# MRCS-12v-power-block.net
KiCad netlist of a schematic drawn in EAGLE
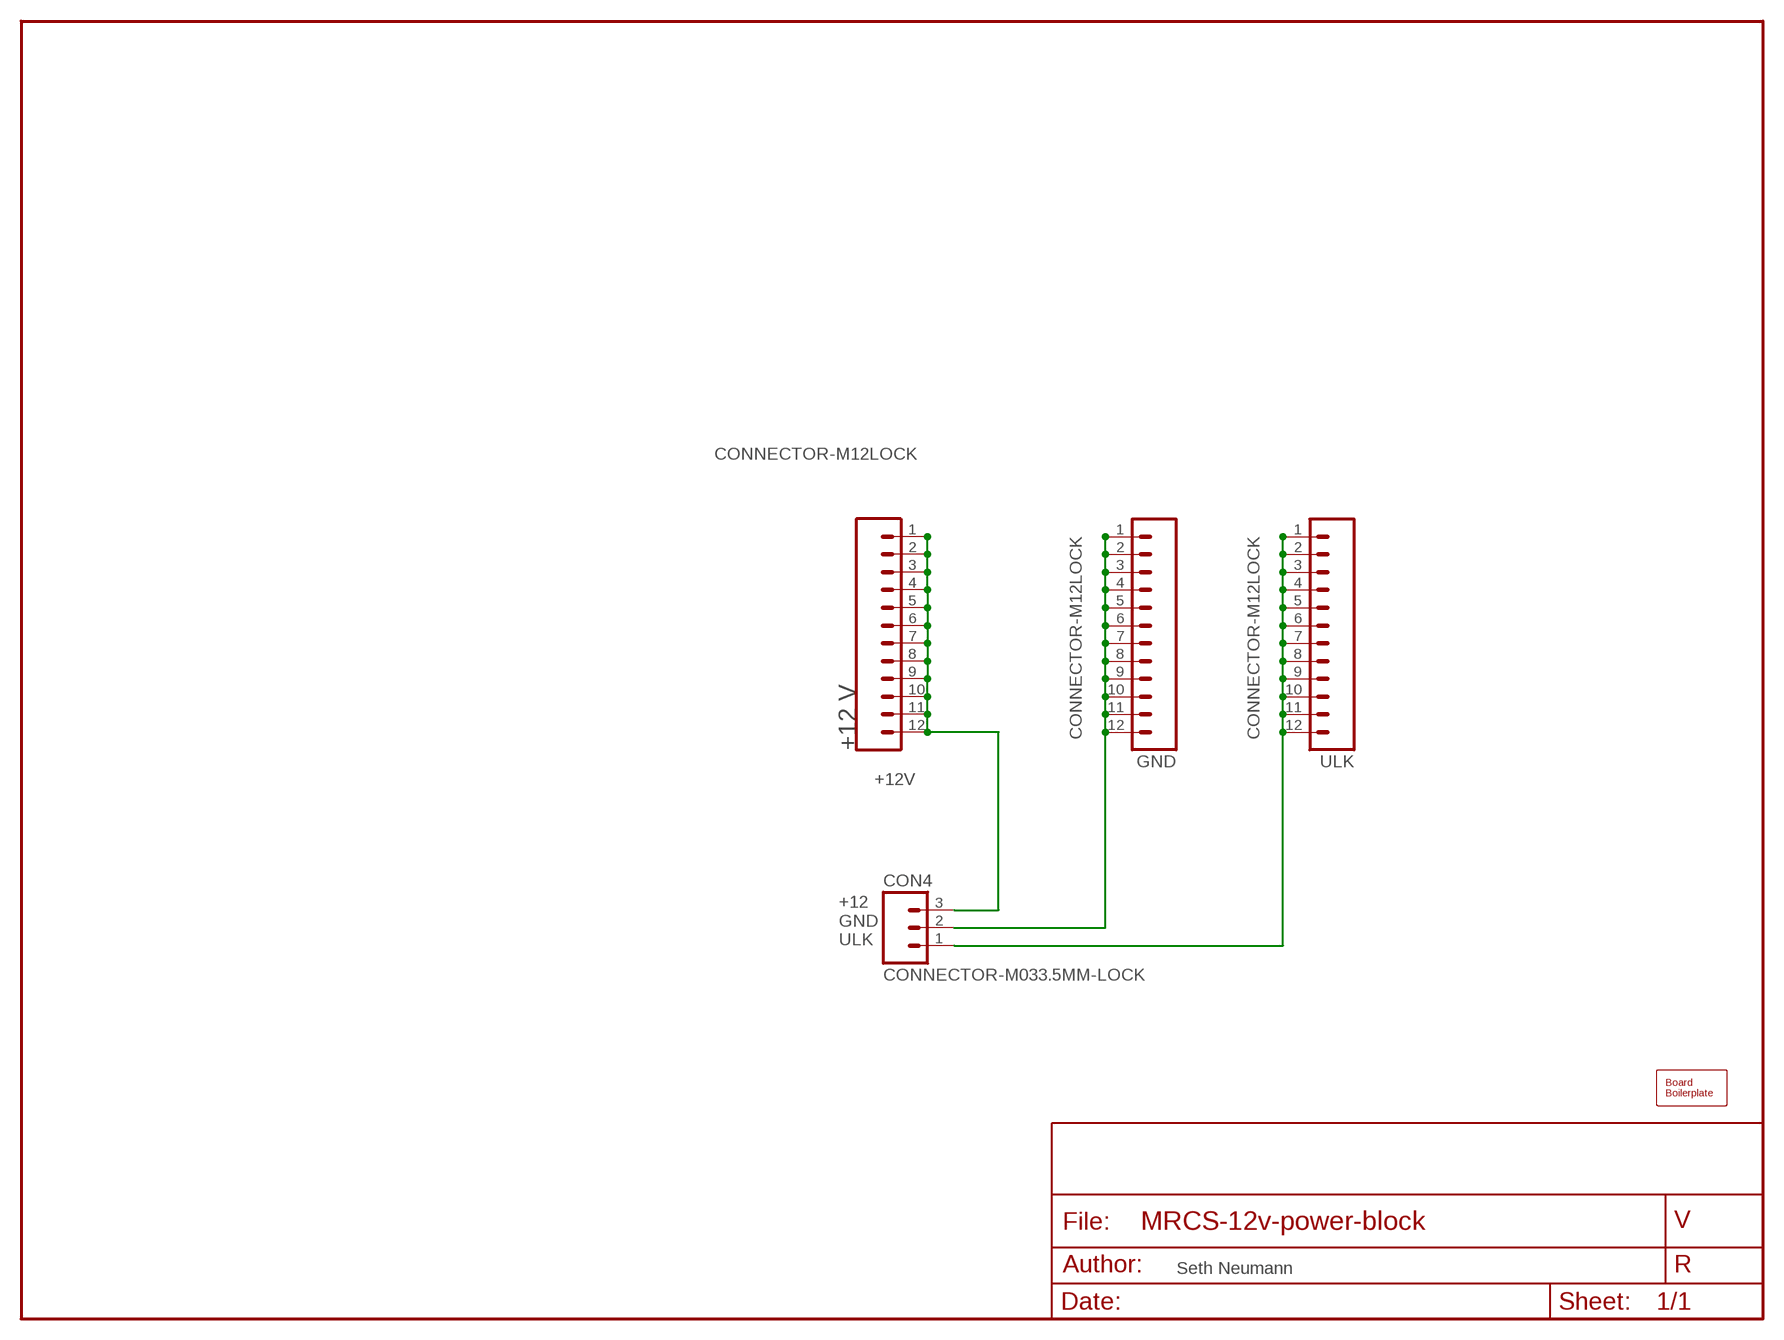
[diagram p0: schematic, sheet 1]

(export (version "E")
  (design (tool "Eeschema 10.0.6"))
  (components
    (comp (ref "+12V")
      (value "CONNECTOR-M12LOCK")
      (footprint "eagle-import:1X12_LOCK")
      (libsource (lib "eagle-import") (part "CONNECTOR-M12LOCK"))
    )
    (comp (ref "BOARD1")
      (value "BOARD50X50")
      (footprint "eagle-import:BOARD-SEEED5X5")
      (libsource (lib "eagle-import") (part "BOARD50X50"))
    )
    (comp (ref "CON4")
      (value "CONNECTOR-M033.5MM-LOCK")
      (footprint "eagle-import:SCREWTERMINAL-3.5MM-3_LOCK.007S")
      (libsource (lib "eagle-import") (part "CONNECTOR-M033.5MM-LOCK"))
    )
    (comp (ref "GND")
      (value "CONNECTOR-M12LOCK")
      (footprint "eagle-import:1X12_LOCK")
      (libsource (lib "eagle-import") (part "CONNECTOR-M12LOCK"))
    )
    (comp (ref "ULK")
      (value "CONNECTOR-M12LOCK")
      (footprint "eagle-import:1X12_LOCK")
      (libsource (lib "eagle-import") (part "CONNECTOR-M12LOCK"))
    )
  )
  (nets
    (net (code "1") (name "Net-(+12V-Pad1)") (class "Default")
      (node (ref "+12V") (pin "1") (pinfunction "1_1") (pintype "passive"))
      (node (ref "+12V") (pin "10") (pinfunction "10_10") (pintype "passive"))
      (node (ref "+12V") (pin "11") (pinfunction "11_11") (pintype "passive"))
      (node (ref "+12V") (pin "12") (pinfunction "12_12") (pintype "passive"))
      (node (ref "+12V") (pin "2") (pinfunction "2_2") (pintype "passive"))
      (node (ref "+12V") (pin "3") (pinfunction "3_3") (pintype "passive"))
      (node (ref "+12V") (pin "4") (pinfunction "4_4") (pintype "passive"))
      (node (ref "+12V") (pin "5") (pinfunction "5_5") (pintype "passive"))
      (node (ref "+12V") (pin "6") (pinfunction "6_6") (pintype "passive"))
      (node (ref "+12V") (pin "7") (pinfunction "7_7") (pintype "passive"))
      (node (ref "+12V") (pin "8") (pinfunction "8_8") (pintype "passive"))
      (node (ref "+12V") (pin "9") (pinfunction "9_9") (pintype "passive"))
      (node (ref "CON4") (pin "3") (pinfunction "3_3") (pintype "passive"))
    )
    (net (code "2") (name "Net-(CON4-Pad1)") (class "Default")
      (node (ref "CON4") (pin "1") (pinfunction "1_1") (pintype "passive"))
      (node (ref "ULK") (pin "1") (pinfunction "1_1") (pintype "passive"))
      (node (ref "ULK") (pin "10") (pinfunction "10_10") (pintype "passive"))
      (node (ref "ULK") (pin "11") (pinfunction "11_11") (pintype "passive"))
      (node (ref "ULK") (pin "12") (pinfunction "12_12") (pintype "passive"))
      (node (ref "ULK") (pin "2") (pinfunction "2_2") (pintype "passive"))
      (node (ref "ULK") (pin "3") (pinfunction "3_3") (pintype "passive"))
      (node (ref "ULK") (pin "4") (pinfunction "4_4") (pintype "passive"))
      (node (ref "ULK") (pin "5") (pinfunction "5_5") (pintype "passive"))
      (node (ref "ULK") (pin "6") (pinfunction "6_6") (pintype "passive"))
      (node (ref "ULK") (pin "7") (pinfunction "7_7") (pintype "passive"))
      (node (ref "ULK") (pin "8") (pinfunction "8_8") (pintype "passive"))
      (node (ref "ULK") (pin "9") (pinfunction "9_9") (pintype "passive"))
    )
    (net (code "3") (name "Net-(CON4-Pad2)") (class "Default")
      (node (ref "CON4") (pin "2") (pinfunction "2_2") (pintype "passive"))
      (node (ref "GND") (pin "1") (pinfunction "1_1") (pintype "passive"))
      (node (ref "GND") (pin "10") (pinfunction "10_10") (pintype "passive"))
      (node (ref "GND") (pin "11") (pinfunction "11_11") (pintype "passive"))
      (node (ref "GND") (pin "12") (pinfunction "12_12") (pintype "passive"))
      (node (ref "GND") (pin "2") (pinfunction "2_2") (pintype "passive"))
      (node (ref "GND") (pin "3") (pinfunction "3_3") (pintype "passive"))
      (node (ref "GND") (pin "4") (pinfunction "4_4") (pintype "passive"))
      (node (ref "GND") (pin "5") (pinfunction "5_5") (pintype "passive"))
      (node (ref "GND") (pin "6") (pinfunction "6_6") (pintype "passive"))
      (node (ref "GND") (pin "7") (pinfunction "7_7") (pintype "passive"))
      (node (ref "GND") (pin "8") (pinfunction "8_8") (pintype "passive"))
      (node (ref "GND") (pin "9") (pinfunction "9_9") (pintype "passive"))
    )
  )
)
